# eeZeeProp.net
KiCad netlist of a schematic drawn in EAGLE
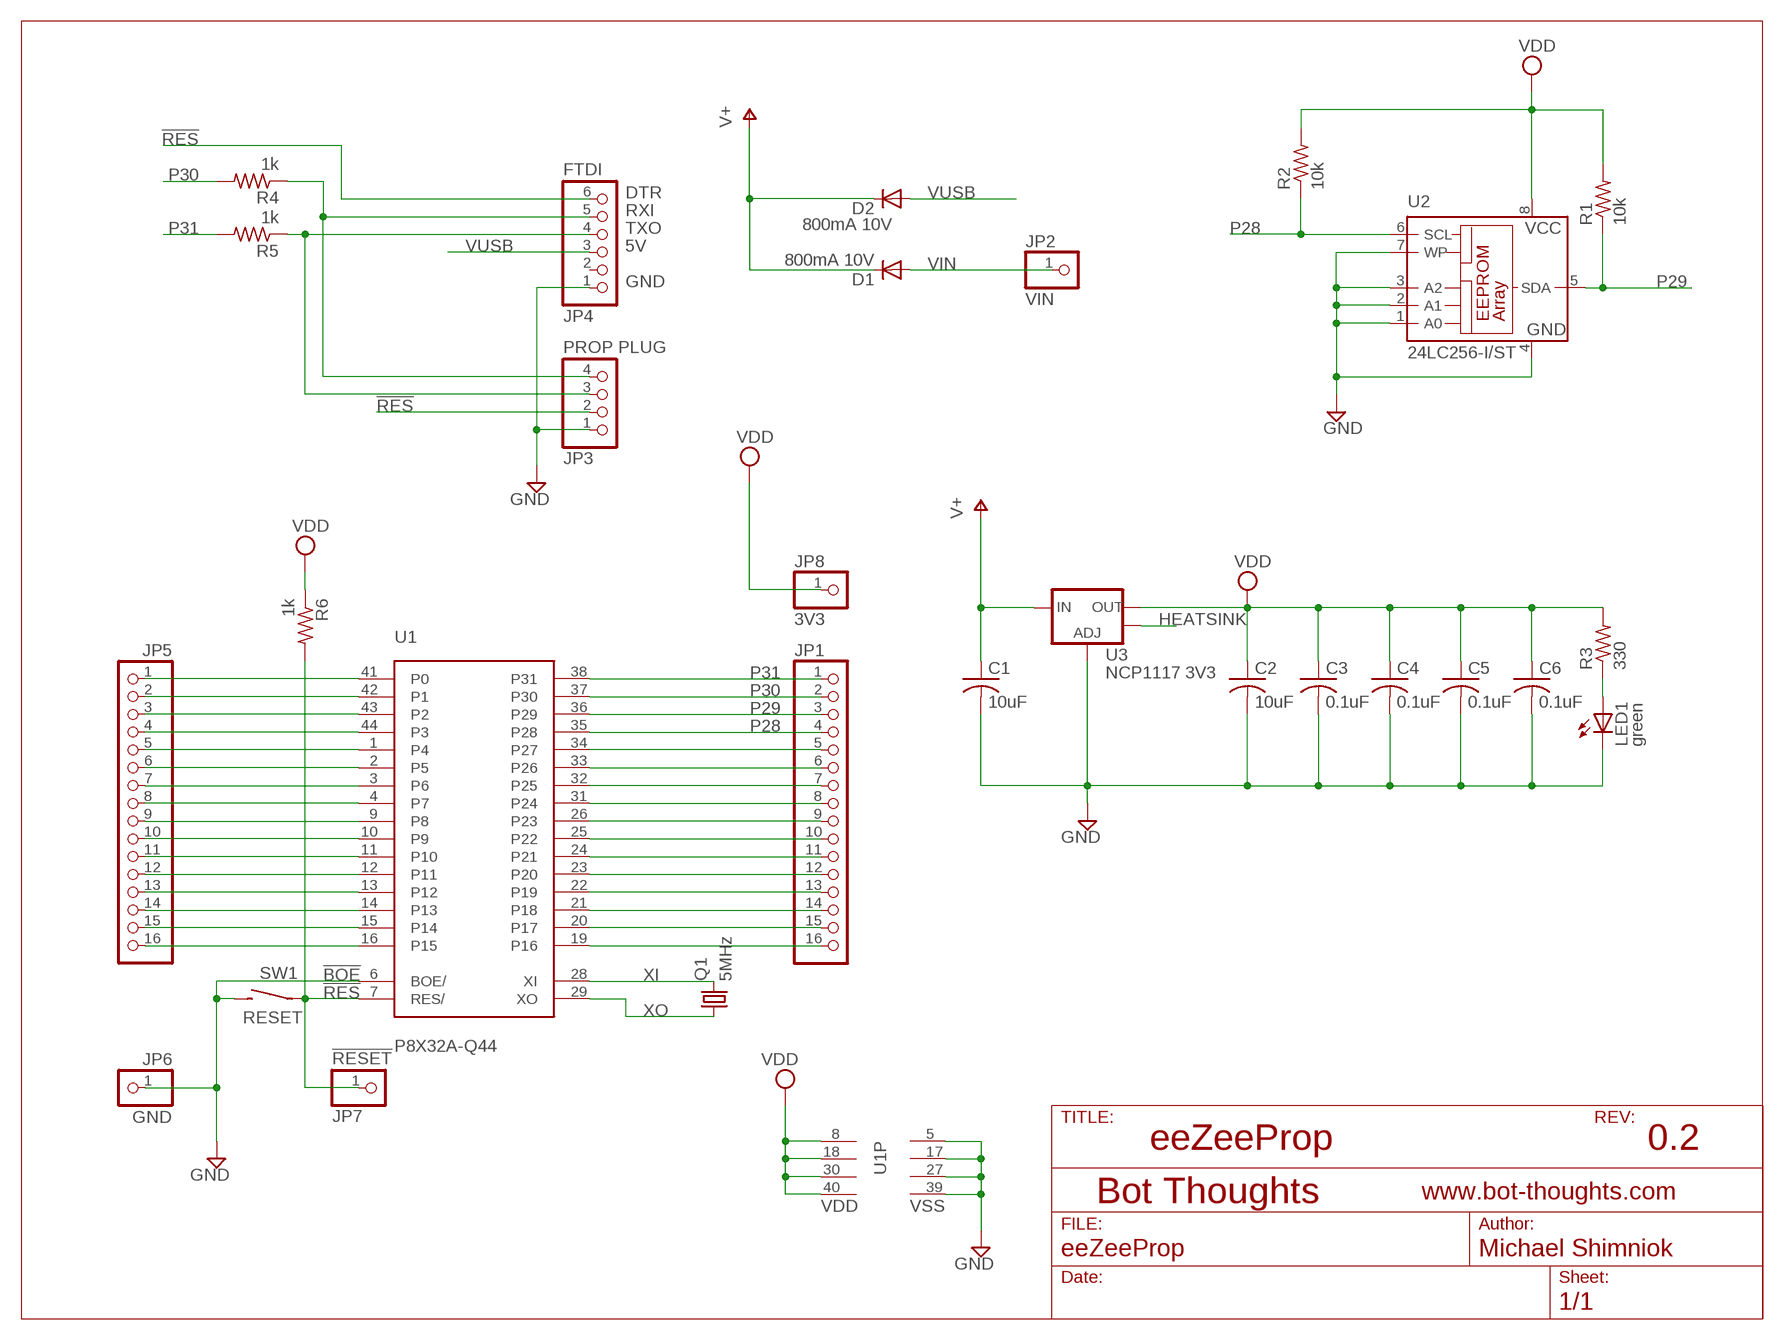
[diagram p0: schematic, sheet 1]

(export (version "E")
  (design (tool "Eeschema 10.0.6"))
  (components
    (comp (ref "C1")
      (value "10uF")
      (footprint "eagle-import:C1206")
      (fields (field (name "PARTNO") "T491A106M006AT"))
      (libsource (lib "eagle-import") (part "C-USC1206"))
    )
    (comp (ref "C2")
      (value "10uF")
      (footprint "eagle-import:C1206")
      (fields (field (name "PARTNO") "T491A106M006AT"))
      (libsource (lib "eagle-import") (part "C-USC1206"))
    )
    (comp (ref "C3")
      (value "0.1uF")
      (footprint "eagle-import:C0603")
      (fields (field (name "PARTNO") "0603YC104KAT2A"))
      (libsource (lib "eagle-import") (part "C-USC0603"))
    )
    (comp (ref "C4")
      (value "0.1uF")
      (footprint "eagle-import:C0603")
      (fields (field (name "PARTNO") "0603YC104KAT2A"))
      (libsource (lib "eagle-import") (part "C-USC0603"))
    )
    (comp (ref "C5")
      (value "0.1uF")
      (footprint "eagle-import:C0603")
      (fields (field (name "PARTNO") "0603YC104KAT2A"))
      (libsource (lib "eagle-import") (part "C-USC0603"))
    )
    (comp (ref "C6")
      (value "0.1uF")
      (footprint "eagle-import:C0603")
      (fields (field (name "PARTNO") "0603YC104KAT2A"))
      (libsource (lib "eagle-import") (part "C-USC0603"))
    )
    (comp (ref "D1")
      (value "800mA 10V")
      (footprint "eagle-import:SOD323-R")
      (fields (field (name "PARTNO") "PMEG2015EA,115"))
      (libsource (lib "eagle-import") (part "DIODE-SOD323-R"))
    )
    (comp (ref "D2")
      (value "800mA 10V")
      (footprint "eagle-import:SOD323-R")
      (fields (field (name "PARTNO") "PMEG2015EA,115"))
      (libsource (lib "eagle-import") (part "DIODE-SOD323-R"))
    )
    (comp (ref "JP1")
      (value "PINHD-1X16_2.54-S")
      (footprint "eagle-import:1X16-S")
      (libsource (lib "eagle-import") (part "PINHD-1X16_2.54-S"))
    )
    (comp (ref "JP2")
      (value "VIN")
      (footprint "eagle-import:1X01")
      (libsource (lib "eagle-import") (part "PINHD-1X01_2.54"))
    )
    (comp (ref "JP3")
      (value "PROP PLUG")
      (footprint "eagle-import:1X04_90-S")
      (libsource (lib "eagle-import") (part "PINHD-1X04_2.54-90°-S"))
    )
    (comp (ref "JP4")
      (value "FTDI")
      (footprint "eagle-import:1X06-S")
      (fields (field (name "PARTNO") "2211S-06G"))
      (libsource (lib "eagle-import") (part "PINHD-1X06_2.54-S"))
    )
    (comp (ref "JP5")
      (value "PINHD-1X16_2.54-S")
      (footprint "eagle-import:1X16-S")
      (libsource (lib "eagle-import") (part "PINHD-1X16_2.54-S"))
    )
    (comp (ref "JP6")
      (value "GND")
      (footprint "eagle-import:1X01")
      (libsource (lib "eagle-import") (part "PINHD-1X01_2.54"))
    )
    (comp (ref "JP7")
      (value "!RESET")
      (footprint "eagle-import:1X01")
      (libsource (lib "eagle-import") (part "PINHD-1X01_2.54"))
    )
    (comp (ref "JP8")
      (value "3V3")
      (footprint "eagle-import:1X01")
      (libsource (lib "eagle-import") (part "PINHD-1X01_2.54"))
    )
    (comp (ref "LED1")
      (value "green")
      (footprint "eagle-import:CHIPLED_1206")
      (fields (field (name "PARTNO") "LG N971-KN-1"))
      (libsource (lib "eagle-import") (part "LEDCHIPLED_1206"))
    )
    (comp (ref "Q1")
      (value "5MHz")
      (footprint "eagle-import:HC49U-V")
      (fields (field (name "OC_FARNELL") "1666969") (field (name "PARTNO") "HC49US-5.000MABJ-UB"))
      (libsource (lib "eagle-import") (part "CRYSTALHC49U-V"))
    )
    (comp (ref "R1")
      (value "10k")
      (footprint "eagle-import:R0603")
      (fields (field (name "PARTNO") "ERJ-3GEYJ103V"))
      (libsource (lib "eagle-import") (part "R-US_R0603"))
    )
    (comp (ref "R2")
      (value "10k")
      (footprint "eagle-import:R0603")
      (fields (field (name "PARTNO") "ERJ-3GEYJ103V"))
      (libsource (lib "eagle-import") (part "R-US_R0603"))
    )
    (comp (ref "R3")
      (value "330")
      (footprint "eagle-import:R0603")
      (fields (field (name "PARTNO") "ERJ-3GEYJ331V"))
      (libsource (lib "eagle-import") (part "R-US_R0603"))
    )
    (comp (ref "R4")
      (value "1k")
      (footprint "eagle-import:R0603")
      (fields (field (name "PARTNO") "RC0603JR-071KL"))
      (libsource (lib "eagle-import") (part "R-US_R0603"))
    )
    (comp (ref "R5")
      (value "1k")
      (footprint "eagle-import:R0603")
      (fields (field (name "PARTNO") "RC0603JR-071KL"))
      (libsource (lib "eagle-import") (part "R-US_R0603"))
    )
    (comp (ref "R6")
      (value "1k")
      (footprint "eagle-import:R0603")
      (fields (field (name "PARTNO") "RC0603JR-071KL"))
      (libsource (lib "eagle-import") (part "R-US_R0603"))
    )
    (comp (ref "SW1")
      (value "RESET")
      (footprint "eagle-import:6MMTACTILE_RECT")
      (fields (field (name "PARTNO") "MJTP1243"))
      (libsource (lib "eagle-import") (part "SPST_TAC_RECT1"))
    )
    (comp (ref "U1")
      (value "P8X32A-Q44")
      (footprint "eagle-import:P8X32A-Q44")
      (fields (field (name "PARTNO") "P8X32A-Q44"))
      (libsource (lib "eagle-import") (part "P8X32A-Q44"))
    )
    (comp (ref "U2")
      (value "24LC256-I/ST")
      (footprint "eagle-import:SO-08")
      (fields
        (field (name "MF") "MICROCHIP")
        (field (name "MPN") "24LC128-I/SNG")
        (field (name "MF_1") "OnSemi")
        (field (name "MPN_1") "CAT24C256WI-GT3")
        (field (name "PARTNO") "CAT24C256WI-GT3")
      )
      (libsource (lib "eagle-import") (part "24SNLC128"))
    )
    (comp (ref "U3")
      (value "NCP1117 3V3")
      (footprint "eagle-import:SOT223")
      (fields (field (name "PARTNO") "NCP1117ST33T3G"))
      (libsource (lib "eagle-import") (part "V_REG_LM1117SOT223"))
    )
  )
  (nets
    (net (code "1") (name "/HEATSINK") (class "Default")
      (node (ref "U3") (pin "4") (pinfunction "OUT_4") (pintype "output"))
    )
    (net (code "2") (name "/P28") (class "Default")
      (node (ref "JP1") (pin "4") (pinfunction "4_4") (pintype "passive"))
      (node (ref "R2") (pin "1") (pinfunction "1_1") (pintype "passive"))
      (node (ref "U1") (pin "35") (pinfunction "P28_35") (pintype "bidirectional"))
      (node (ref "U2") (pin "6") (pinfunction "SCL_6") (pintype "input"))
    )
    (net (code "3") (name "/P29") (class "Default")
      (node (ref "JP1") (pin "3") (pinfunction "3_3") (pintype "passive"))
      (node (ref "R1") (pin "1") (pinfunction "1_1") (pintype "passive"))
      (node (ref "U1") (pin "36") (pinfunction "P29_36") (pintype "bidirectional"))
      (node (ref "U2") (pin "5") (pinfunction "SDA_5") (pintype "bidirectional"))
    )
    (net (code "4") (name "/P30") (class "Default")
      (node (ref "JP1") (pin "2") (pinfunction "2_2") (pintype "passive"))
      (node (ref "R4") (pin "2") (pinfunction "2_2") (pintype "passive"))
      (node (ref "U1") (pin "37") (pinfunction "P30_37") (pintype "bidirectional"))
    )
    (net (code "5") (name "/P31") (class "Default")
      (node (ref "JP1") (pin "1") (pinfunction "1_1") (pintype "passive"))
      (node (ref "R5") (pin "2") (pinfunction "2_2") (pintype "passive"))
      (node (ref "U1") (pin "38") (pinfunction "P31_38") (pintype "bidirectional"))
    )
    (net (code "6") (name "/VIN") (class "Default")
      (node (ref "D1") (pin "A") (pinfunction "A_A") (pintype "passive"))
      (node (ref "JP2") (pin "1") (pinfunction "1_1") (pintype "passive"))
    )
    (net (code "7") (name "/VUSB") (class "Default")
      (node (ref "D2") (pin "A") (pinfunction "A_A") (pintype "passive"))
      (node (ref "JP4") (pin "3") (pinfunction "3_3") (pintype "passive"))
    )
    (net (code "8") (name "/XI") (class "Default")
      (node (ref "Q1") (pin "2") (pinfunction "2_2") (pintype "passive"))
      (node (ref "U1") (pin "28") (pinfunction "XI_28") (pintype "input"))
    )
    (net (code "9") (name "/XO") (class "Default")
      (node (ref "Q1") (pin "1") (pinfunction "1_1") (pintype "passive"))
      (node (ref "U1") (pin "29") (pinfunction "XO_29") (pintype "output"))
    )
    (net (code "10") (name "/~{RES}") (class "Default")
      (node (ref "JP3") (pin "2") (pinfunction "2_2") (pintype "passive"))
      (node (ref "JP4") (pin "6") (pinfunction "6_6") (pintype "passive"))
      (node (ref "JP7") (pin "1") (pinfunction "1_1") (pintype "passive"))
      (node (ref "R6") (pin "2") (pinfunction "2_2") (pintype "passive"))
      (node (ref "SW1") (pin "P$1") (pinfunction "P_P$1") (pintype "passive"))
      (node (ref "U1") (pin "7") (pinfunction "RES/_7") (pintype "bidirectional"))
    )
    (net (code "11") (name "GND") (class "Default")
      (node (ref "C1") (pin "2") (pinfunction "2_2") (pintype "passive"))
      (node (ref "C2") (pin "2") (pinfunction "2_2") (pintype "passive"))
      (node (ref "C3") (pin "2") (pinfunction "2_2") (pintype "passive"))
      (node (ref "C4") (pin "2") (pinfunction "2_2") (pintype "passive"))
      (node (ref "C5") (pin "2") (pinfunction "2_2") (pintype "passive"))
      (node (ref "C6") (pin "2") (pinfunction "2_2") (pintype "passive"))
      (node (ref "JP3") (pin "1") (pinfunction "1_1") (pintype "passive"))
      (node (ref "JP4") (pin "1") (pinfunction "1_1") (pintype "passive"))
      (node (ref "JP6") (pin "1") (pinfunction "1_1") (pintype "passive"))
      (node (ref "LED1") (pin "C") (pinfunction "C_C") (pintype "passive"))
      (node (ref "SW1") (pin "P$2") (pinfunction "S_P$2") (pintype "passive"))
      (node (ref "U1") (pin "17") (pinfunction "VSS_17") (pintype "power_in"))
      (node (ref "U1") (pin "27") (pinfunction "VSS_27") (pintype "power_in"))
      (node (ref "U1") (pin "39") (pinfunction "VSS_39") (pintype "power_in"))
      (node (ref "U1") (pin "5") (pinfunction "VSS_5") (pintype "power_in"))
      (node (ref "U1") (pin "6") (pinfunction "BOE/_6") (pintype "input"))
      (node (ref "U2") (pin "1") (pinfunction "A0_1") (pintype "input"))
      (node (ref "U2") (pin "2") (pinfunction "A1_2") (pintype "input"))
      (node (ref "U2") (pin "3") (pinfunction "A2_3") (pintype "input"))
      (node (ref "U2") (pin "4") (pinfunction "GND_4") (pintype "power_in"))
      (node (ref "U2") (pin "7") (pinfunction "WP_7") (pintype "input"))
      (node (ref "U3") (pin "1") (pinfunction "ADJ_1") (pintype "input"))
    )
    (net (code "12") (name "Net-(JP3-Pad3)") (class "Default")
      (node (ref "JP3") (pin "3") (pinfunction "3_3") (pintype "passive"))
      (node (ref "JP4") (pin "4") (pinfunction "4_4") (pintype "passive"))
      (node (ref "R5") (pin "1") (pinfunction "1_1") (pintype "passive"))
    )
    (net (code "13") (name "Net-(JP3-Pad4)") (class "Default")
      (node (ref "JP3") (pin "4") (pinfunction "4_4") (pintype "passive"))
      (node (ref "JP4") (pin "5") (pinfunction "5_5") (pintype "passive"))
      (node (ref "R4") (pin "1") (pinfunction "1_1") (pintype "passive"))
    )
    (net (code "14") (name "Net-(LED1-PadA)") (class "Default")
      (node (ref "LED1") (pin "A") (pinfunction "A_A") (pintype "passive"))
      (node (ref "R3") (pin "1") (pinfunction "1_1") (pintype "passive"))
    )
    (net (code "15") (name "Net-(U1B-P0)") (class "Default")
      (node (ref "JP5") (pin "1") (pinfunction "1_1") (pintype "passive"))
      (node (ref "U1") (pin "41") (pinfunction "P0_41") (pintype "bidirectional"))
    )
    (net (code "16") (name "Net-(U1B-P1)") (class "Default")
      (node (ref "JP5") (pin "2") (pinfunction "2_2") (pintype "passive"))
      (node (ref "U1") (pin "42") (pinfunction "P1_42") (pintype "bidirectional"))
    )
    (net (code "17") (name "Net-(U1B-P2)") (class "Default")
      (node (ref "JP5") (pin "3") (pinfunction "3_3") (pintype "passive"))
      (node (ref "U1") (pin "43") (pinfunction "P2_43") (pintype "bidirectional"))
    )
    (net (code "18") (name "Net-(U1B-P3)") (class "Default")
      (node (ref "JP5") (pin "4") (pinfunction "4_4") (pintype "passive"))
      (node (ref "U1") (pin "44") (pinfunction "P3_44") (pintype "bidirectional"))
    )
    (net (code "19") (name "Net-(U1B-P4)") (class "Default")
      (node (ref "JP5") (pin "5") (pinfunction "5_5") (pintype "passive"))
      (node (ref "U1") (pin "1") (pinfunction "P4_1") (pintype "bidirectional"))
    )
    (net (code "20") (name "Net-(U1B-P5)") (class "Default")
      (node (ref "JP5") (pin "6") (pinfunction "6_6") (pintype "passive"))
      (node (ref "U1") (pin "2") (pinfunction "P5_2") (pintype "bidirectional"))
    )
    (net (code "21") (name "Net-(U1B-P6)") (class "Default")
      (node (ref "JP5") (pin "7") (pinfunction "7_7") (pintype "passive"))
      (node (ref "U1") (pin "3") (pinfunction "P6_3") (pintype "bidirectional"))
    )
    (net (code "22") (name "Net-(U1B-P7)") (class "Default")
      (node (ref "JP5") (pin "8") (pinfunction "8_8") (pintype "passive"))
      (node (ref "U1") (pin "4") (pinfunction "P7_4") (pintype "bidirectional"))
    )
    (net (code "23") (name "Net-(U1B-P8)") (class "Default")
      (node (ref "JP5") (pin "9") (pinfunction "9_9") (pintype "passive"))
      (node (ref "U1") (pin "9") (pinfunction "P8_9") (pintype "bidirectional"))
    )
    (net (code "24") (name "Net-(U1B-P9)") (class "Default")
      (node (ref "JP5") (pin "10") (pinfunction "10_10") (pintype "passive"))
      (node (ref "U1") (pin "10") (pinfunction "P9_10") (pintype "bidirectional"))
    )
    (net (code "25") (name "Net-(U1B-P10)") (class "Default")
      (node (ref "JP5") (pin "11") (pinfunction "11_11") (pintype "passive"))
      (node (ref "U1") (pin "11") (pinfunction "P10_11") (pintype "bidirectional"))
    )
    (net (code "26") (name "Net-(U1B-P11)") (class "Default")
      (node (ref "JP5") (pin "12") (pinfunction "12_12") (pintype "passive"))
      (node (ref "U1") (pin "12") (pinfunction "P11_12") (pintype "bidirectional"))
    )
    (net (code "27") (name "Net-(U1B-P12)") (class "Default")
      (node (ref "JP5") (pin "13") (pinfunction "13_13") (pintype "passive"))
      (node (ref "U1") (pin "13") (pinfunction "P12_13") (pintype "bidirectional"))
    )
    (net (code "28") (name "Net-(U1B-P13)") (class "Default")
      (node (ref "JP5") (pin "14") (pinfunction "14_14") (pintype "passive"))
      (node (ref "U1") (pin "14") (pinfunction "P13_14") (pintype "bidirectional"))
    )
    (net (code "29") (name "Net-(U1B-P14)") (class "Default")
      (node (ref "JP5") (pin "15") (pinfunction "15_15") (pintype "passive"))
      (node (ref "U1") (pin "15") (pinfunction "P14_15") (pintype "bidirectional"))
    )
    (net (code "30") (name "Net-(U1B-P15)") (class "Default")
      (node (ref "JP5") (pin "16") (pinfunction "16_16") (pintype "passive"))
      (node (ref "U1") (pin "16") (pinfunction "P15_16") (pintype "bidirectional"))
    )
    (net (code "31") (name "Net-(U1B-P16)") (class "Default")
      (node (ref "JP1") (pin "16") (pinfunction "16_16") (pintype "passive"))
      (node (ref "U1") (pin "19") (pinfunction "P16_19") (pintype "bidirectional"))
    )
    (net (code "32") (name "Net-(U1B-P17)") (class "Default")
      (node (ref "JP1") (pin "15") (pinfunction "15_15") (pintype "passive"))
      (node (ref "U1") (pin "20") (pinfunction "P17_20") (pintype "bidirectional"))
    )
    (net (code "33") (name "Net-(U1B-P18)") (class "Default")
      (node (ref "JP1") (pin "14") (pinfunction "14_14") (pintype "passive"))
      (node (ref "U1") (pin "21") (pinfunction "P18_21") (pintype "bidirectional"))
    )
    (net (code "34") (name "Net-(U1B-P19)") (class "Default")
      (node (ref "JP1") (pin "13") (pinfunction "13_13") (pintype "passive"))
      (node (ref "U1") (pin "22") (pinfunction "P19_22") (pintype "bidirectional"))
    )
    (net (code "35") (name "Net-(U1B-P20)") (class "Default")
      (node (ref "JP1") (pin "12") (pinfunction "12_12") (pintype "passive"))
      (node (ref "U1") (pin "23") (pinfunction "P20_23") (pintype "bidirectional"))
    )
    (net (code "36") (name "Net-(U1B-P21)") (class "Default")
      (node (ref "JP1") (pin "11") (pinfunction "11_11") (pintype "passive"))
      (node (ref "U1") (pin "24") (pinfunction "P21_24") (pintype "bidirectional"))
    )
    (net (code "37") (name "Net-(U1B-P22)") (class "Default")
      (node (ref "JP1") (pin "10") (pinfunction "10_10") (pintype "passive"))
      (node (ref "U1") (pin "25") (pinfunction "P22_25") (pintype "bidirectional"))
    )
    (net (code "38") (name "Net-(U1B-P23)") (class "Default")
      (node (ref "JP1") (pin "9") (pinfunction "9_9") (pintype "passive"))
      (node (ref "U1") (pin "26") (pinfunction "P23_26") (pintype "bidirectional"))
    )
    (net (code "39") (name "Net-(U1B-P24)") (class "Default")
      (node (ref "JP1") (pin "8") (pinfunction "8_8") (pintype "passive"))
      (node (ref "U1") (pin "31") (pinfunction "P24_31") (pintype "bidirectional"))
    )
    (net (code "40") (name "Net-(U1B-P25)") (class "Default")
      (node (ref "JP1") (pin "7") (pinfunction "7_7") (pintype "passive"))
      (node (ref "U1") (pin "32") (pinfunction "P25_32") (pintype "bidirectional"))
    )
    (net (code "41") (name "Net-(U1B-P26)") (class "Default")
      (node (ref "JP1") (pin "6") (pinfunction "6_6") (pintype "passive"))
      (node (ref "U1") (pin "33") (pinfunction "P26_33") (pintype "bidirectional"))
    )
    (net (code "42") (name "Net-(U1B-P27)") (class "Default")
      (node (ref "JP1") (pin "5") (pinfunction "5_5") (pintype "passive"))
      (node (ref "U1") (pin "34") (pinfunction "P27_34") (pintype "bidirectional"))
    )
    (net (code "43") (name "V+") (class "Default")
      (node (ref "C1") (pin "1") (pinfunction "1_1") (pintype "passive"))
      (node (ref "D1") (pin "C") (pinfunction "C_C") (pintype "passive"))
      (node (ref "D2") (pin "C") (pinfunction "C_C") (pintype "passive"))
      (node (ref "U3") (pin "3") (pinfunction "IN_3") (pintype "input"))
    )
    (net (code "44") (name "VDD") (class "Default")
      (node (ref "C2") (pin "1") (pinfunction "1_1") (pintype "passive"))
      (node (ref "C3") (pin "1") (pinfunction "1_1") (pintype "passive"))
      (node (ref "C4") (pin "1") (pinfunction "1_1") (pintype "passive"))
      (node (ref "C5") (pin "1") (pinfunction "1_1") (pintype "passive"))
      (node (ref "C6") (pin "1") (pinfunction "1_1") (pintype "passive"))
      (node (ref "JP8") (pin "1") (pinfunction "1_1") (pintype "passive"))
      (node (ref "R1") (pin "2") (pinfunction "2_2") (pintype "passive"))
      (node (ref "R2") (pin "2") (pinfunction "2_2") (pintype "passive"))
      (node (ref "R3") (pin "2") (pinfunction "2_2") (pintype "passive"))
      (node (ref "R6") (pin "1") (pinfunction "1_1") (pintype "passive"))
      (node (ref "U1") (pin "18") (pinfunction "VDD_18") (pintype "power_in"))
      (node (ref "U1") (pin "30") (pinfunction "VDD_30") (pintype "power_in"))
      (node (ref "U1") (pin "40") (pinfunction "VDD_40") (pintype "power_in"))
      (node (ref "U1") (pin "8") (pinfunction "VDD_8") (pintype "power_in"))
      (node (ref "U2") (pin "8") (pinfunction "VCC_8") (pintype "power_in"))
      (node (ref "U3") (pin "2") (pinfunction "OUT_2") (pintype "output"))
    )
    (net (code "45") (name "unconnected-(JP4-Pad2)") (class "Default")
      (node (ref "JP4") (pin "2") (pinfunction "2_2") (pintype "passive"))
    )
  )
)
